# LP55231_LED_DRIVER.net
KiCad netlist of a schematic drawn in Altium Designer
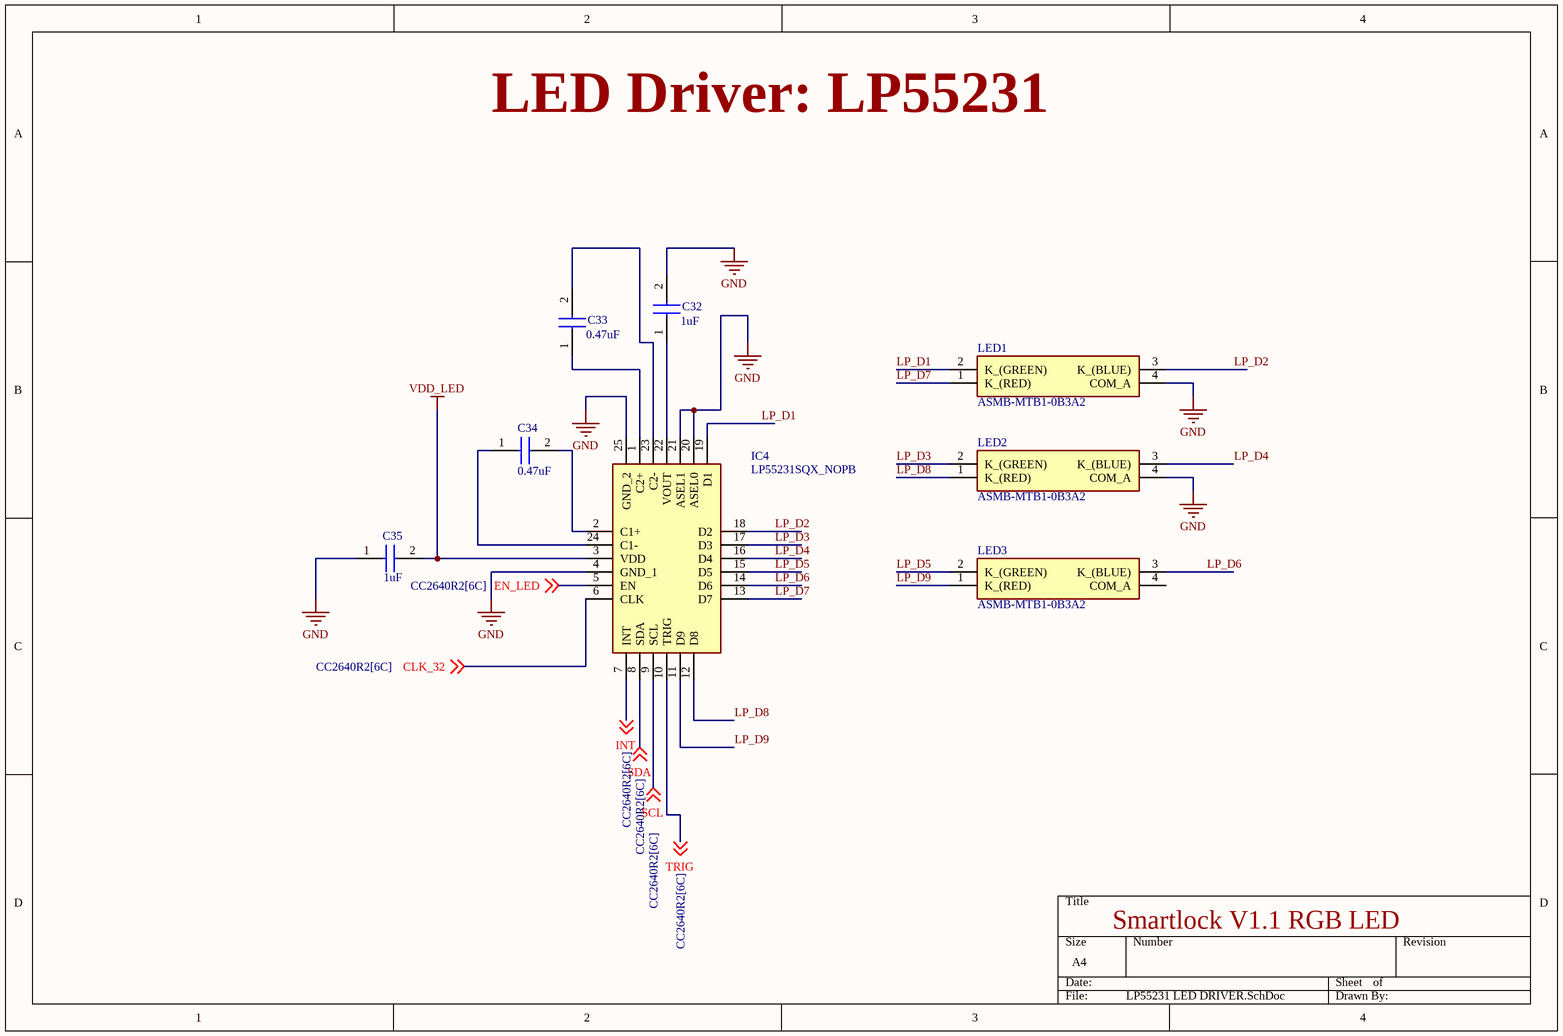
[diagram p0: LP55231 LED DRIVER.SchDoc]

(export (version "E")
  (design (tool "Eeschema 10.0.6"))
  (components
    (comp (ref "C32")
      (value "1uF")
      (footprint "Smart_lockV1.1:CAPC1005X55N")
      (description "Capacitor 1uF 10V")
      (fields
        (field (name "MANUFACTURER_PART_NUMBER") "GRM155R61A105KE15D")
        (field (name "MOUSER PART NUMBER") "81-GRM155R61A105KE15")
      )
      (libsource (lib "Smart_lockV1.1") (part "GRM155R61A105KE15D"))
    )
    (comp (ref "C33")
      (value "0.47uF")
      (footprint "Smart_lockV1.1:CAPC1005X55N")
      (description "Capacitor 0.47uF 10V X5R")
      (fields
        (field (name "MANUFACTURER_PART_NUMBER") "C1005X5R1A474K050BB")
        (field (name "MOUSER PART NUMBER") "810-C1005X5R1A474K")
      )
      (libsource (lib "*") (part "C1005X5R1A474K050BB"))
    )
    (comp (ref "C34")
      (value "0.47uF")
      (footprint "Smart_lockV1.1:CAPC1005X55N")
      (description "Capacitor 0.47uF 10V X5R")
      (fields
        (field (name "MANUFACTURER_PART_NUMBER") "C1005X5R1A474K050BB")
        (field (name "MOUSER PART NUMBER") "810-C1005X5R1A474K")
      )
      (libsource (lib "*") (part "C1005X5R1A474K050BB"))
    )
    (comp (ref "C35")
      (value "1uF")
      (footprint "Smart_lockV1.1:CAPC1005X55N")
      (description "Capacitor 1uF 10V X5R")
      (fields
        (field (name "MANUFACTURER_PART_NUMBER") "GRM155R61A105KE15D")
        (field (name "MOUSER PART NUMBER") "81-GRM155R61A105KE15")
      )
      (libsource (lib "Smart_lockV1.1") (part "GRM155R61A105KE15D"))
    )
    (comp (ref "IC4")
      (value "LP55231SQX_NOPB")
      (footprint "Smart_lockV1.1:QFN50P400X400X80-25N")
      (description "Integrated Circuit")
      (fields
        (field (name "MANUFACTURER_PART_NUMBER") "LP55231SQX/NOPB")
        (field (name "MOUSER PART NUMBER") "595-LP55231SQX/NOPB")
      )
      (libsource (lib "Smart_lockV1.1") (part "LP55231SQX_NOPB"))
    )
    (comp (ref "LED1")
      (value "ASMB-MTB1-0B3A2")
      (footprint "Smart_lockV1.1:ASMBMTB10B3A2")
      (description "LED")
      (fields (field (name "MOUSER PART NUMBER") "630-ASMB-MTB1-0B3A2"))
      (libsource (lib "*") (part "ASMB-MTB1-0B3A2"))
    )
    (comp (ref "LED2")
      (value "ASMB-MTB1-0B3A2")
      (footprint "Smart_lockV1.1:ASMBMTB10B3A2")
      (description "LED")
      (fields (field (name "MOUSER PART NUMBER") "630-ASMB-MTB1-0B3A2"))
      (libsource (lib "*") (part "ASMB-MTB1-0B3A2"))
    )
    (comp (ref "LED3")
      (value "ASMB-MTB1-0B3A2")
      (footprint "Smart_lockV1.1:ASMBMTB10B3A2")
      (description "LED")
      (fields (field (name "MOUSER PART NUMBER") "630-ASMB-MTB1-0B3A2"))
      (libsource (lib "*") (part "ASMB-MTB1-0B3A2"))
    )
  )
  (nets
    (net (code "1") (name "/LP_D1") (class "Default")
      (node (ref "IC4") (pin "19") (pinfunction "D1_19") (pintype "passive"))
      (node (ref "LED1") (pin "2") (pinfunction "K_(GREEN)_2") (pintype "passive"))
    )
    (net (code "2") (name "/LP_D2") (class "Default")
      (node (ref "IC4") (pin "18") (pinfunction "D2_18") (pintype "passive"))
      (node (ref "LED1") (pin "3") (pinfunction "K_(BLUE)_3") (pintype "passive"))
    )
    (net (code "3") (name "/LP_D3") (class "Default")
      (node (ref "IC4") (pin "17") (pinfunction "D3_17") (pintype "passive"))
      (node (ref "LED2") (pin "2") (pinfunction "K_(GREEN)_2") (pintype "passive"))
    )
    (net (code "4") (name "/LP_D4") (class "Default")
      (node (ref "IC4") (pin "16") (pinfunction "D4_16") (pintype "passive"))
      (node (ref "LED2") (pin "3") (pinfunction "K_(BLUE)_3") (pintype "passive"))
    )
    (net (code "5") (name "/LP_D5") (class "Default")
      (node (ref "IC4") (pin "15") (pinfunction "D5_15") (pintype "passive"))
      (node (ref "LED3") (pin "2") (pinfunction "K_(GREEN)_2") (pintype "passive"))
    )
    (net (code "6") (name "/LP_D6") (class "Default")
      (node (ref "IC4") (pin "14") (pinfunction "D6_14") (pintype "passive"))
      (node (ref "LED3") (pin "3") (pinfunction "K_(BLUE)_3") (pintype "passive"))
    )
    (net (code "7") (name "/LP_D7") (class "Default")
      (node (ref "IC4") (pin "13") (pinfunction "D7_13") (pintype "passive"))
      (node (ref "LED1") (pin "1") (pinfunction "K_(RED)_1") (pintype "passive"))
    )
    (net (code "8") (name "/LP_D8") (class "Default")
      (node (ref "IC4") (pin "12") (pinfunction "D8_12") (pintype "passive"))
      (node (ref "LED2") (pin "1") (pinfunction "K_(RED)_1") (pintype "passive"))
    )
    (net (code "9") (name "/LP_D9") (class "Default")
      (node (ref "IC4") (pin "11") (pinfunction "D9_11") (pintype "passive"))
      (node (ref "LED3") (pin "1") (pinfunction "K_(RED)_1") (pintype "passive"))
    )
    (net (code "10") (name "CLK_32") (class "Default")
      (node (ref "IC4") (pin "6") (pinfunction "CLK_6") (pintype "passive"))
    )
    (net (code "11") (name "EN_LED") (class "Default")
      (node (ref "IC4") (pin "5") (pinfunction "EN_5") (pintype "passive"))
    )
    (net (code "12") (name "GND") (class "Default")
      (node (ref "C32") (pin "2") (pinfunction "2_2") (pintype "passive"))
      (node (ref "C35") (pin "1") (pinfunction "1_1") (pintype "passive"))
      (node (ref "IC4") (pin "20") (pinfunction "ASEL0_20") (pintype "passive"))
      (node (ref "IC4") (pin "21") (pinfunction "ASEL1_21") (pintype "passive"))
      (node (ref "IC4") (pin "25") (pinfunction "GND_2_25") (pintype "passive"))
      (node (ref "IC4") (pin "4") (pinfunction "GND_1_4") (pintype "passive"))
      (node (ref "LED1") (pin "4") (pinfunction "COM_A_4") (pintype "passive"))
      (node (ref "LED2") (pin "4") (pinfunction "COM_A_4") (pintype "passive"))
    )
    (net (code "13") (name "INT") (class "Default")
      (node (ref "IC4") (pin "7") (pinfunction "INT_7") (pintype "passive"))
    )
    (net (code "14") (name "Net-(IC4-C1+)") (class "Default")
      (node (ref "C34") (pin "2") (pinfunction "2_2") (pintype "passive"))
      (node (ref "IC4") (pin "2") (pinfunction "C1+_2") (pintype "passive"))
    )
    (net (code "15") (name "Net-(IC4-C1-)") (class "Default")
      (node (ref "C34") (pin "1") (pinfunction "1_1") (pintype "passive"))
      (node (ref "IC4") (pin "24") (pinfunction "C1-_24") (pintype "passive"))
    )
    (net (code "16") (name "Net-(IC4-C2+)") (class "Default")
      (node (ref "C33") (pin "1") (pinfunction "1_1") (pintype "passive"))
      (node (ref "IC4") (pin "1") (pinfunction "C2+_1") (pintype "passive"))
    )
    (net (code "17") (name "Net-(IC4-C2-)") (class "Default")
      (node (ref "C33") (pin "2") (pinfunction "2_2") (pintype "passive"))
      (node (ref "IC4") (pin "23") (pinfunction "C2-_23") (pintype "passive"))
    )
    (net (code "18") (name "Net-(IC4-VOUT)") (class "Default")
      (node (ref "C32") (pin "1") (pinfunction "1_1") (pintype "passive"))
      (node (ref "IC4") (pin "22") (pinfunction "VOUT_22") (pintype "passive"))
    )
    (net (code "19") (name "SCL") (class "Default")
      (node (ref "IC4") (pin "9") (pinfunction "SCL_9") (pintype "passive"))
    )
    (net (code "20") (name "SDA") (class "Default")
      (node (ref "IC4") (pin "8") (pinfunction "SDA_8") (pintype "passive"))
    )
    (net (code "21") (name "TRIG") (class "Default")
      (node (ref "IC4") (pin "10") (pinfunction "TRIG_10") (pintype "passive"))
    )
    (net (code "22") (name "VDD_LED") (class "Default")
      (node (ref "C35") (pin "2") (pinfunction "2_2") (pintype "passive"))
      (node (ref "IC4") (pin "3") (pinfunction "VDD_3") (pintype "passive"))
    )
    (net (code "23") (name "unconnected-(LED3-COM_A-Pad4)") (class "Default")
      (node (ref "LED3") (pin "4") (pinfunction "COM_A_4") (pintype "passive"))
    )
  )
)
